# MAX485_BREAKOUT_BOARD_v1.net
KiCad netlist of a schematic drawn in EAGLE
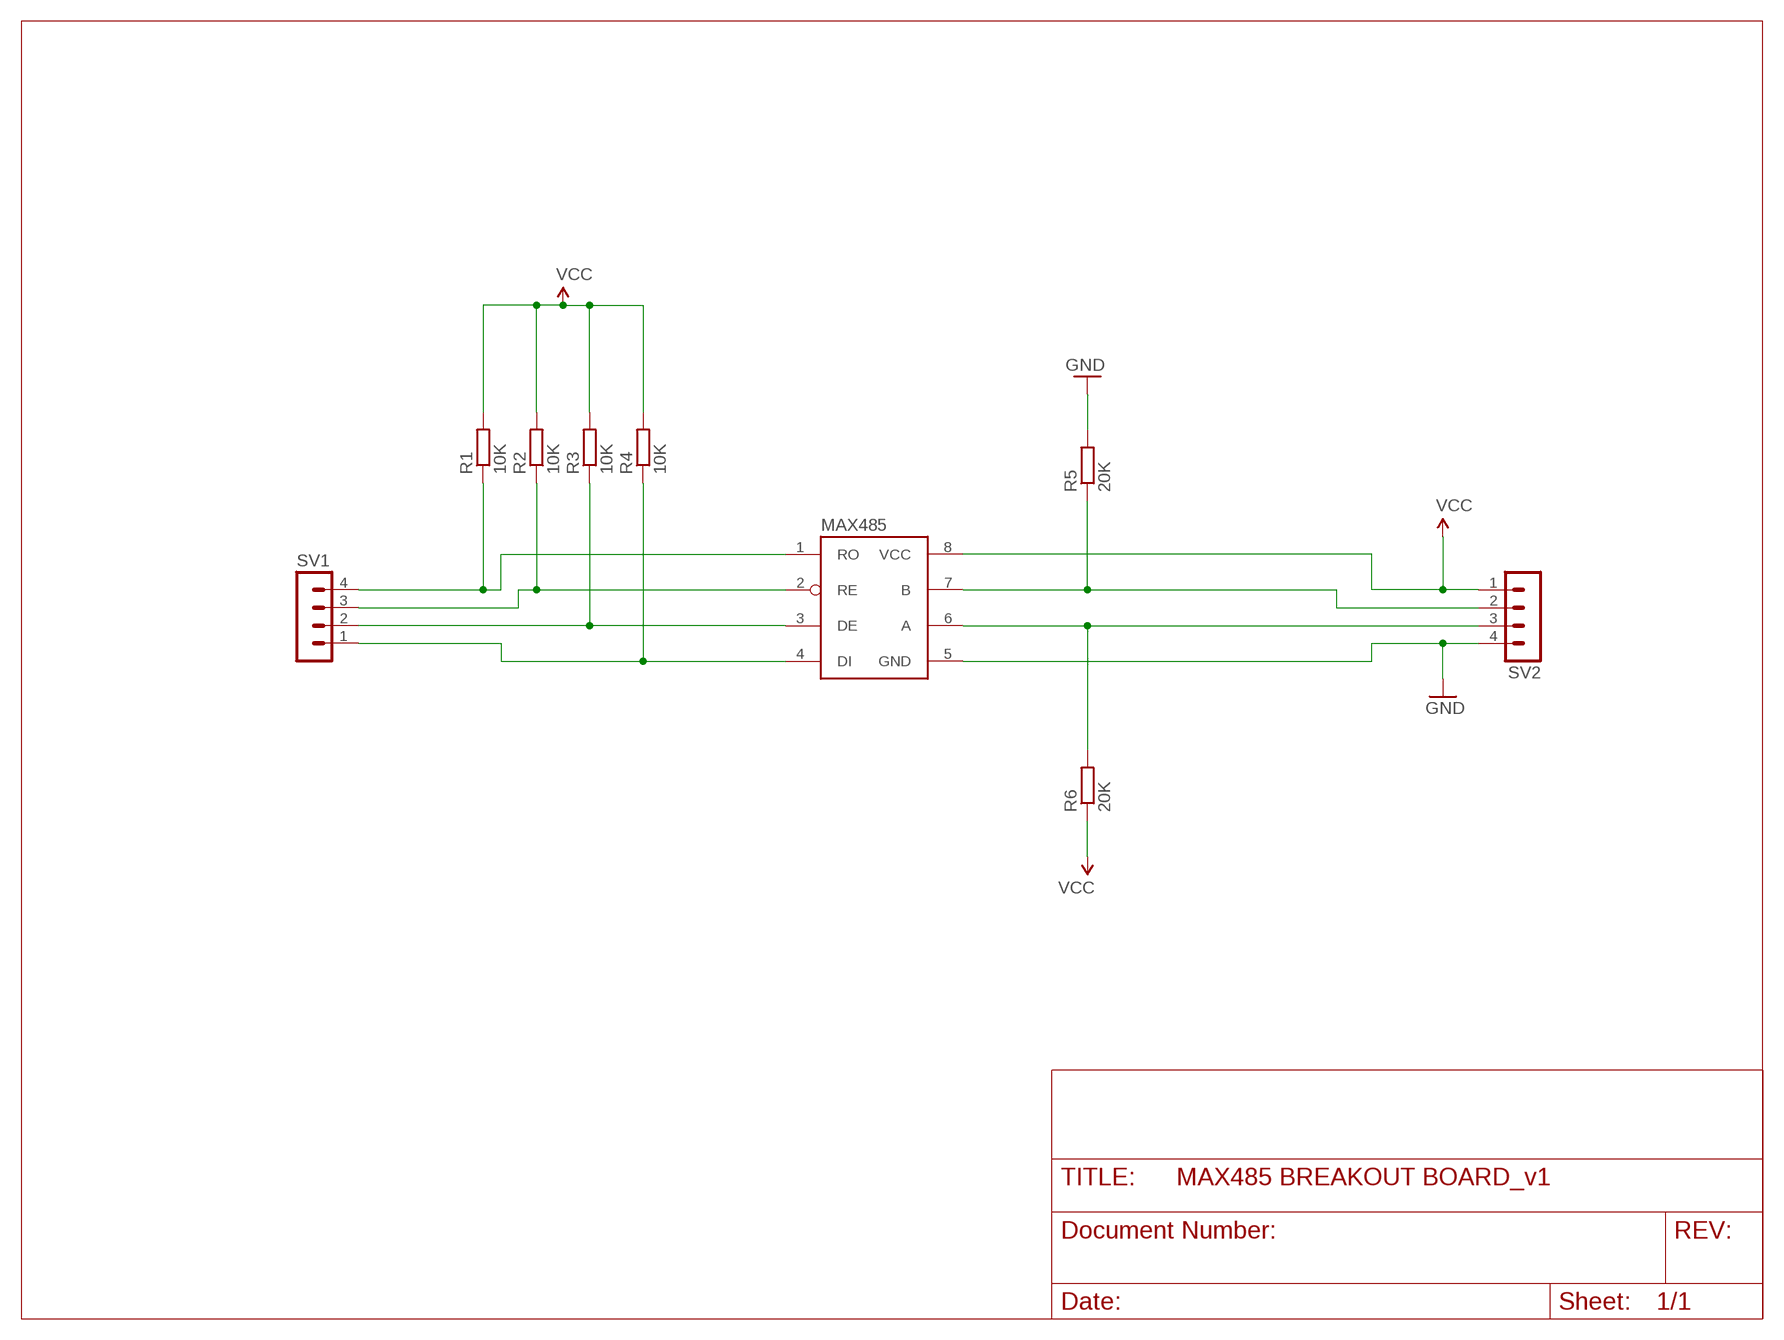
[diagram p0: schematic, sheet 1]

(export (version "E")
  (design (tool "Eeschema 10.0.6"))
  (components
    (comp (ref "MAX485")
      (value "CINVESTAV_ADM1485")
      (footprint "eagle-import:CINVESTAV_SOIC8")
      (libsource (lib "eagle-import") (part "CINVESTAV_ADM1485"))
    )
    (comp (ref "R1")
      (value "10K")
      (footprint "eagle-import:RCL_R1206")
      (libsource (lib "eagle-import") (part "RCL_R-EU_R1206"))
    )
    (comp (ref "R2")
      (value "10K")
      (footprint "eagle-import:RCL_R1206")
      (libsource (lib "eagle-import") (part "RCL_R-EU_R1206"))
    )
    (comp (ref "R3")
      (value "10K")
      (footprint "eagle-import:RCL_R1206")
      (libsource (lib "eagle-import") (part "RCL_R-EU_R1206"))
    )
    (comp (ref "R4")
      (value "10K")
      (footprint "eagle-import:RCL_R1206")
      (libsource (lib "eagle-import") (part "RCL_R-EU_R1206"))
    )
    (comp (ref "R5")
      (value "20K")
      (footprint "eagle-import:RCL_R1206")
      (libsource (lib "eagle-import") (part "RCL_R-EU_R1206"))
    )
    (comp (ref "R6")
      (value "20K")
      (footprint "eagle-import:RCL_R1206")
      (libsource (lib "eagle-import") (part "RCL_R-EU_R1206"))
    )
    (comp (ref "SV1")
      (value "MA04-1")
      (footprint "eagle-import:MA04-1")
      (libsource (lib "eagle-import") (part "MA04-1"))
    )
    (comp (ref "SV2")
      (value "MA04-1")
      (footprint "eagle-import:MA04-1")
      (libsource (lib "eagle-import") (part "MA04-1"))
    )
  )
  (nets
    (net (code "1") (name "GND") (class "Default")
      (node (ref "MAX485") (pin "5") (pinfunction "GND_5") (pintype "power_in"))
      (node (ref "R5") (pin "2") (pinfunction "2_2") (pintype "passive"))
      (node (ref "SV2") (pin "4") (pinfunction "4_4") (pintype "passive"))
    )
    (net (code "2") (name "Net-(MAX485-A)") (class "Default")
      (node (ref "MAX485") (pin "6") (pinfunction "A_6") (pintype "bidirectional"))
      (node (ref "R6") (pin "2") (pinfunction "2_2") (pintype "passive"))
      (node (ref "SV2") (pin "3") (pinfunction "3_3") (pintype "passive"))
    )
    (net (code "3") (name "Net-(MAX485-B)") (class "Default")
      (node (ref "MAX485") (pin "7") (pinfunction "B_7") (pintype "bidirectional"))
      (node (ref "R5") (pin "1") (pinfunction "1_1") (pintype "passive"))
      (node (ref "SV2") (pin "2") (pinfunction "2_2") (pintype "passive"))
    )
    (net (code "4") (name "Net-(MAX485-DE)") (class "Default")
      (node (ref "MAX485") (pin "3") (pinfunction "DE_3") (pintype "input"))
      (node (ref "R3") (pin "1") (pinfunction "1_1") (pintype "passive"))
      (node (ref "SV1") (pin "2") (pinfunction "2_2") (pintype "passive"))
    )
    (net (code "5") (name "Net-(MAX485-DI)") (class "Default")
      (node (ref "MAX485") (pin "4") (pinfunction "DI_4") (pintype "input"))
      (node (ref "R4") (pin "1") (pinfunction "1_1") (pintype "passive"))
      (node (ref "SV1") (pin "1") (pinfunction "1_1") (pintype "passive"))
    )
    (net (code "6") (name "Net-(MAX485-RE)") (class "Default")
      (node (ref "MAX485") (pin "2") (pinfunction "RE_2") (pintype "input"))
      (node (ref "R2") (pin "1") (pinfunction "1_1") (pintype "passive"))
      (node (ref "SV1") (pin "3") (pinfunction "3_3") (pintype "passive"))
    )
    (net (code "7") (name "Net-(MAX485-RO)") (class "Default")
      (node (ref "MAX485") (pin "1") (pinfunction "RO_1") (pintype "output"))
      (node (ref "R1") (pin "1") (pinfunction "1_1") (pintype "passive"))
      (node (ref "SV1") (pin "4") (pinfunction "4_4") (pintype "passive"))
    )
    (net (code "8") (name "VCC") (class "Default")
      (node (ref "MAX485") (pin "8") (pinfunction "VCC_8") (pintype "power_in"))
      (node (ref "R1") (pin "2") (pinfunction "2_2") (pintype "passive"))
      (node (ref "R2") (pin "2") (pinfunction "2_2") (pintype "passive"))
      (node (ref "R3") (pin "2") (pinfunction "2_2") (pintype "passive"))
      (node (ref "R4") (pin "2") (pinfunction "2_2") (pintype "passive"))
      (node (ref "R6") (pin "1") (pinfunction "1_1") (pintype "passive"))
      (node (ref "SV2") (pin "1") (pinfunction "1_1") (pintype "passive"))
    )
  )
)
